# halfbridge.net
KiCad netlist of a schematic drawn in EAGLE
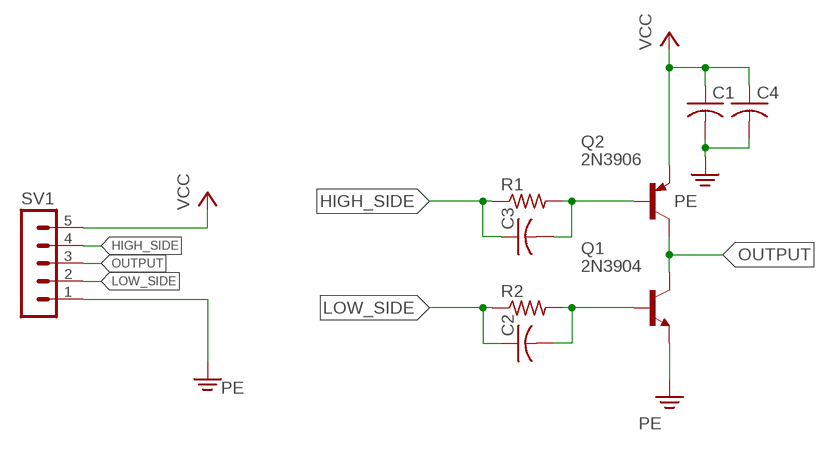
[diagram p0: schematic, sheet 1]

(export (version "E")
  (design (tool "Eeschema 10.0.6"))
  (components
    (comp (ref "C1")
      (value "C-US050-024X044")
      (footprint "eagle-import:C050-024X044")
      (libsource (lib "eagle-import") (part "C-US050-024X044"))
    )
    (comp (ref "C2")
      (value "C-US050-024X044")
      (footprint "eagle-import:C050-024X044")
      (libsource (lib "eagle-import") (part "C-US050-024X044"))
    )
    (comp (ref "C3")
      (value "C-US050-024X044")
      (footprint "eagle-import:C050-024X044")
      (libsource (lib "eagle-import") (part "C-US050-024X044"))
    )
    (comp (ref "C4")
      (value "C-US050-024X044")
      (footprint "eagle-import:C050-024X044")
      (libsource (lib "eagle-import") (part "C-US050-024X044"))
    )
    (comp (ref "Q1")
      (value "2N3904")
      (footprint "eagle-import:TO-92")
      (libsource (lib "eagle-import") (part "2N3904"))
    )
    (comp (ref "Q2")
      (value "2N3906")
      (footprint "eagle-import:TO-92")
      (libsource (lib "eagle-import") (part "2N3906"))
    )
    (comp (ref "R1")
      (value "R-US_0204/5")
      (footprint "eagle-import:0204_5")
      (libsource (lib "eagle-import") (part "R-US_0204/5"))
    )
    (comp (ref "R2")
      (value "R-US_0204/5")
      (footprint "eagle-import:0204_5")
      (libsource (lib "eagle-import") (part "R-US_0204/5"))
    )
    (comp (ref "SV1")
      (value "MA05-1")
      (footprint "eagle-import:MA05-1")
      (libsource (lib "eagle-import") (part "MA05-1"))
    )
  )
  (nets
    (net (code "1") (name "HIGH_SIDE") (class "Default")
      (node (ref "C3") (pin "1") (pinfunction "1_1") (pintype "passive"))
      (node (ref "R1") (pin "1") (pinfunction "1_1") (pintype "passive"))
      (node (ref "SV1") (pin "4") (pinfunction "4_4") (pintype "passive"))
    )
    (net (code "2") (name "LOW_SIDE") (class "Default")
      (node (ref "C2") (pin "1") (pinfunction "1_1") (pintype "passive"))
      (node (ref "R2") (pin "1") (pinfunction "1_1") (pintype "passive"))
      (node (ref "SV1") (pin "2") (pinfunction "2_2") (pintype "passive"))
    )
    (net (code "3") (name "Net-(C2-Pad2)") (class "Default")
      (node (ref "C2") (pin "2") (pinfunction "2_2") (pintype "passive"))
      (node (ref "Q1") (pin "B") (pinfunction "B_B") (pintype "passive"))
      (node (ref "R2") (pin "2") (pinfunction "2_2") (pintype "passive"))
    )
    (net (code "4") (name "Net-(C3-Pad2)") (class "Default")
      (node (ref "C3") (pin "2") (pinfunction "2_2") (pintype "passive"))
      (node (ref "Q2") (pin "B") (pinfunction "B_B") (pintype "passive"))
      (node (ref "R1") (pin "2") (pinfunction "2_2") (pintype "passive"))
    )
    (net (code "5") (name "OUTPUT") (class "Default")
      (node (ref "Q1") (pin "C") (pinfunction "C_C") (pintype "passive"))
      (node (ref "Q2") (pin "C") (pinfunction "C_C") (pintype "passive"))
      (node (ref "SV1") (pin "3") (pinfunction "3_3") (pintype "passive"))
    )
    (net (code "6") (name "PE") (class "Default")
      (node (ref "C1") (pin "2") (pinfunction "2_2") (pintype "passive"))
      (node (ref "C4") (pin "2") (pinfunction "2_2") (pintype "passive"))
      (node (ref "Q1") (pin "E") (pinfunction "E_E") (pintype "passive"))
      (node (ref "SV1") (pin "1") (pinfunction "1_1") (pintype "passive"))
    )
    (net (code "7") (name "VCC") (class "Default")
      (node (ref "C1") (pin "1") (pinfunction "1_1") (pintype "passive"))
      (node (ref "C4") (pin "1") (pinfunction "1_1") (pintype "passive"))
      (node (ref "Q2") (pin "E") (pinfunction "E_E") (pintype "passive"))
      (node (ref "SV1") (pin "5") (pinfunction "5_5") (pintype "passive"))
    )
  )
)
